# BLE_Controller.net
KiCad netlist of a schematic drawn in Altium Designer
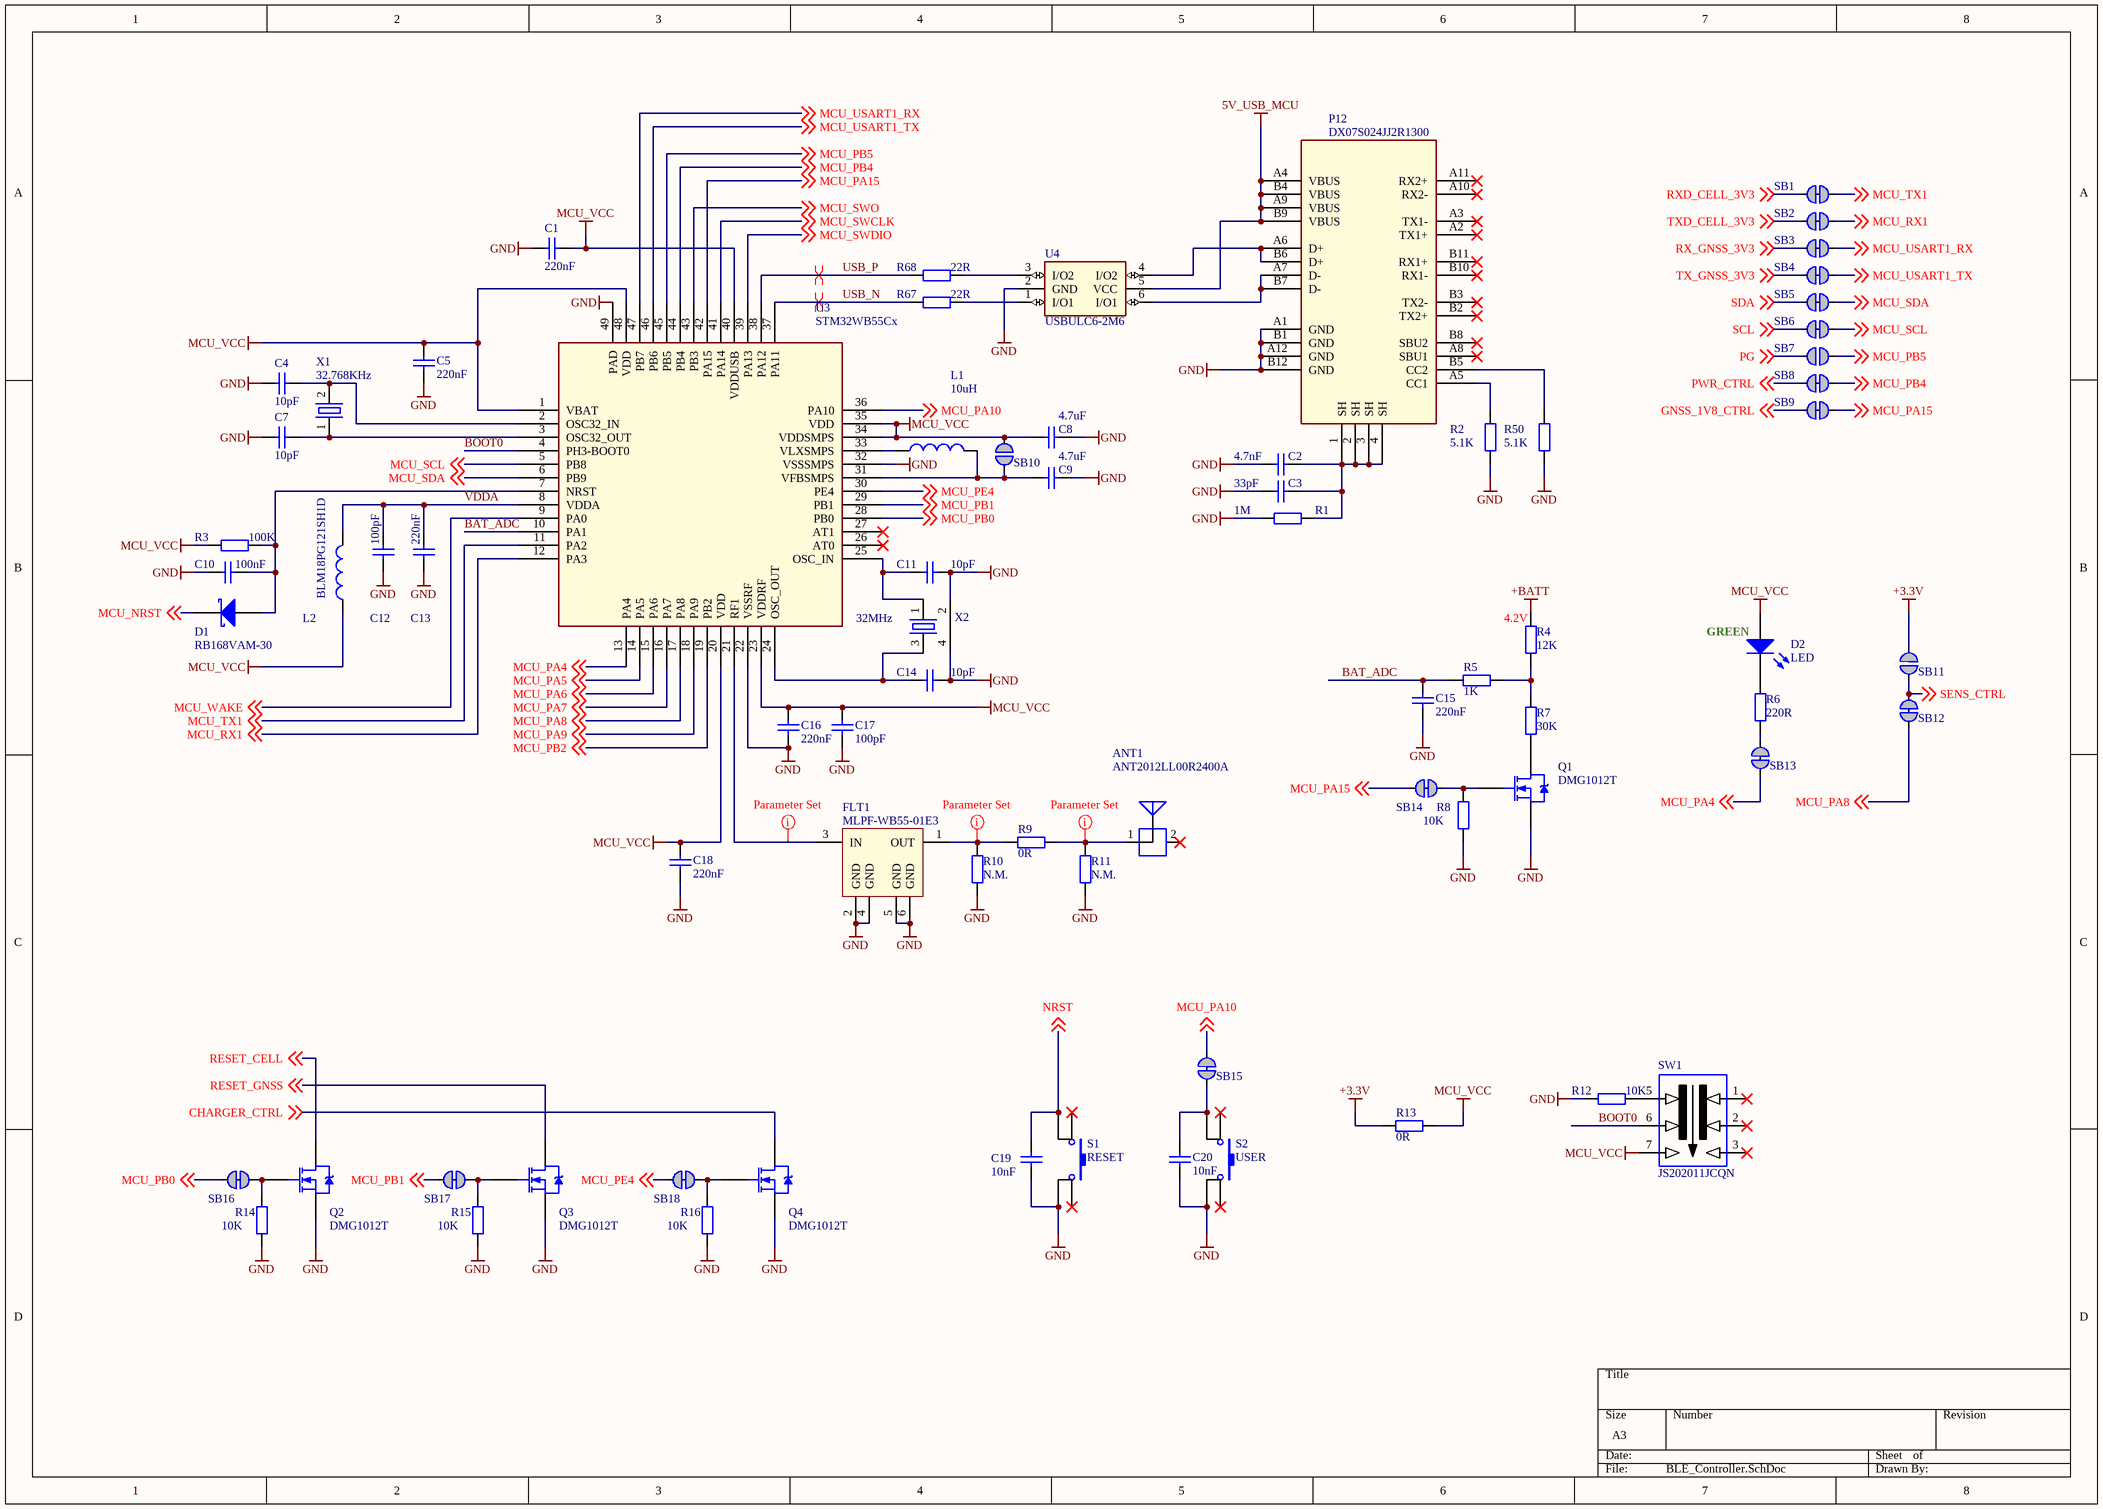
[diagram p0: BLE_Controller.SchDoc]

(export (version "E")
  (design (tool "Eeschema 10.0.6"))
  (components
    (comp (ref "ANT1")
      (value "ANT2012LL00R2400A")
      (footprint "YEGEO_BT_Antena_0805")
      (description "Generic Antenna")
      (fields (field (name "MANUFACTURER") "YAGEO"))
      (libsource (lib "RUT_GE310_GNSS") (part "Antenna"))
    )
    (comp (ref "C1")
      (value "220nF")
      (footprint "C0402")
      (description "Capacitor (Semiconductor SIM Model)")
      (fields
        (field (name "MANUFACTURER") "YAGEO")
        (field (name "MANUFACTURER PART NO.") "CC0402JRNPO9BN100")
      )
      (libsource (lib "Miscellaneous Devices") (part "Cap Semi"))
    )
    (comp (ref "C2")
      (value "4.7nF")
      (footprint "C0402")
      (description "Capacitor (Semiconductor SIM Model)")
      (fields
        (field (name "MANUFACTURER") "YAGEO")
        (field (name "MANUFACTURER PART NO.") "CC0402JRNPO9BN100")
      )
      (libsource (lib "Miscellaneous Devices") (part "Cap Semi"))
    )
    (comp (ref "C3")
      (value "33pF")
      (footprint "C0402")
      (description "Capacitor (Semiconductor SIM Model)")
      (fields
        (field (name "MANUFACTURER") "YAGEO")
        (field (name "MANUFACTURER PART NO.") "CC0402JRNPO9BN100")
      )
      (libsource (lib "Miscellaneous Devices") (part "Cap Semi"))
    )
    (comp (ref "C4")
      (value "10pF")
      (footprint "C0402")
      (description "Capacitor (Semiconductor SIM Model)")
      (fields
        (field (name "MANUFACTURER") "YAGEO")
        (field (name "MANUFACTURER PART NO.") "CC0402JRNPO9BN100")
      )
      (libsource (lib "Miscellaneous Devices") (part "Cap Semi"))
    )
    (comp (ref "C5")
      (value "220nF")
      (footprint "C0402")
      (description "Capacitor (Semiconductor SIM Model)")
      (fields
        (field (name "MANUFACTURER") "YAGEO")
        (field (name "MANUFACTURER PART NO.") "CC0402JRNPO9BN100")
      )
      (libsource (lib "Miscellaneous Devices") (part "Cap Semi"))
    )
    (comp (ref "C7")
      (value "10pF")
      (footprint "C0402")
      (description "Capacitor (Semiconductor SIM Model)")
      (fields
        (field (name "MANUFACTURER") "YAGEO")
        (field (name "MANUFACTURER PART NO.") "CC0402JRNPO9BN100")
      )
      (libsource (lib "Miscellaneous Devices") (part "Cap Semi"))
    )
    (comp (ref "C8")
      (value "4.7uF")
      (footprint "C0402")
      (description "Capacitor (Semiconductor SIM Model)")
      (fields
        (field (name "MANUFACTURER") "YAGEO")
        (field (name "MANUFACTURER PART NO.") "CC0402JRNPO9BN100")
      )
      (libsource (lib "Miscellaneous Devices") (part "Cap Semi"))
    )
    (comp (ref "C9")
      (value "4.7uF")
      (footprint "C0402")
      (description "Capacitor (Semiconductor SIM Model)")
      (fields
        (field (name "MANUFACTURER") "YAGEO")
        (field (name "MANUFACTURER PART NO.") "CC0402JRNPO9BN100")
      )
      (libsource (lib "Miscellaneous Devices") (part "Cap Semi"))
    )
    (comp (ref "C10")
      (value "100nF")
      (footprint "C0402")
      (description "Capacitor (Semiconductor SIM Model)")
      (fields
        (field (name "MANUFACTURER") "YAGEO")
        (field (name "MANUFACTURER PART NO.") "CC0402JRNPO9BN100")
      )
      (libsource (lib "Miscellaneous Devices") (part "Cap Semi"))
    )
    (comp (ref "C11")
      (value "10pF")
      (footprint "C0402")
      (description "Capacitor (Semiconductor SIM Model)")
      (fields
        (field (name "MANUFACTURER") "YAGEO")
        (field (name "MANUFACTURER PART NO.") "CC0402JRNPO9BN100")
      )
      (libsource (lib "Miscellaneous Devices") (part "Cap Semi"))
    )
    (comp (ref "C12")
      (value "100pF")
      (footprint "C0402")
      (description "Capacitor (Semiconductor SIM Model)")
      (fields
        (field (name "MANUFACTURER") "YAGEO")
        (field (name "MANUFACTURER PART NO.") "CC0402JRNPO9BN100")
      )
      (libsource (lib "Miscellaneous Devices") (part "Cap Semi"))
    )
    (comp (ref "C13")
      (value "220nF")
      (footprint "C0402")
      (description "Capacitor (Semiconductor SIM Model)")
      (fields
        (field (name "MANUFACTURER") "YAGEO")
        (field (name "MANUFACTURER PART NO.") "CC0402JRNPO9BN100")
      )
      (libsource (lib "Miscellaneous Devices") (part "Cap Semi"))
    )
    (comp (ref "C14")
      (value "10pF")
      (footprint "C0402")
      (description "Capacitor (Semiconductor SIM Model)")
      (fields
        (field (name "MANUFACTURER") "YAGEO")
        (field (name "MANUFACTURER PART NO.") "CC0402JRNPO9BN100")
      )
      (libsource (lib "Miscellaneous Devices") (part "Cap Semi"))
    )
    (comp (ref "C15")
      (value "220nF")
      (footprint "C0402")
      (description "Capacitor (Semiconductor SIM Model)")
      (fields
        (field (name "MANUFACTURER") "YAGEO")
        (field (name "MANUFACTURER PART NO.") "CC0402KRX5R5BB224")
      )
      (libsource (lib "Miscellaneous Devices") (part "Cap Semi"))
    )
    (comp (ref "C16")
      (value "220nF")
      (footprint "C0402")
      (description "Capacitor (Semiconductor SIM Model)")
      (fields
        (field (name "MANUFACTURER") "YAGEO")
        (field (name "MANUFACTURER PART NO.") "CC0402JRNPO9BN100")
      )
      (libsource (lib "Miscellaneous Devices") (part "Cap Semi"))
    )
    (comp (ref "C17")
      (value "100pF")
      (footprint "C0402")
      (description "Capacitor (Semiconductor SIM Model)")
      (fields
        (field (name "MANUFACTURER") "YAGEO")
        (field (name "MANUFACTURER PART NO.") "CC0402JRNPO9BN100")
      )
      (libsource (lib "Miscellaneous Devices") (part "Cap Semi"))
    )
    (comp (ref "C18")
      (value "220nF")
      (footprint "C0402")
      (description "Capacitor (Semiconductor SIM Model)")
      (fields
        (field (name "MANUFACTURER") "YAGEO")
        (field (name "MANUFACTURER PART NO.") "CC0402JRNPO9BN100")
      )
      (libsource (lib "Miscellaneous Devices") (part "Cap Semi"))
    )
    (comp (ref "C19")
      (value "10nF")
      (footprint "C0402")
      (description "Capacitor (Semiconductor SIM Model)")
      (fields
        (field (name "MANUFACTURER") "Samsung Electronics")
        (field (name "MANUFACTURER PART NO.") "CL05B103KB5NNNC")
      )
      (libsource (lib "Miscellaneous Devices") (part "Cap Semi"))
    )
    (comp (ref "C20")
      (value "10nF")
      (footprint "C0402")
      (description "Capacitor (Semiconductor SIM Model)")
      (fields
        (field (name "MANUFACTURER") "Samsung Electronics")
        (field (name "MANUFACTURER PART NO.") "CL05B103KB5NNNC")
      )
      (libsource (lib "Miscellaneous Devices") (part "Cap Semi"))
    )
    (comp (ref "D1")
      (value "RB168VAM-30")
      (footprint "SOD323")
      (description "Schottky Diode")
      (fields (field (name "MANUFACTURER") "ROHM"))
      (libsource (lib "Miscellaneous Devices") (part "D Schottky"))
    )
    (comp (ref "D2")
      (value "LED")
      (footprint "PICOLED")
      (description "Typical SMD LED")
      (fields (field (name "MANUFACTURER") "ROHM") (field (name "MANUFACTURER PART NO.") "SML-P13PTT86R"))
      (libsource (lib "Miscellaneous Devices") (part "LED2"))
    )
    (comp (ref "FLT1")
      (value "MLPF-WB55-01E3")
      (footprint "Bumpless CSP")
      (description "2.4 GHz low pass filter matched to STM32WB55Cx/Rx")
      (fields (field (name "MANUFACTURER") "STMicroelectronics"))
      (libsource (lib "MLPF-WB55-01E3") (part "MLPF-WB55-01E3"))
    )
    (comp (ref "L1")
      (value "10uH")
      (footprint "L0805")
      (description "Inductor")
      (fields (field (name "MANUFACTURER") "muRata") (field (name "MANUFACTURER PART NO.") "LQM21FN100M70L"))
      (libsource (lib "Miscellaneous Devices") (part "Inductor"))
    )
    (comp (ref "L2")
      (value "BLM18PG121SH1D")
      (footprint "L0603")
      (description "Inductor")
      (fields (field (name "MANUFACTURER") "muRata"))
      (libsource (lib "Miscellaneous Devices") (part "Inductor"))
    )
    (comp (ref "P12")
      (value "DX07S024JJ2R1300")
      (footprint "DX07_USB_C")
      (description "24P USB C DUAL SMT ON BOARD")
      (fields (field (name "MANUFACTURER") "JAE"))
      (libsource (lib "DX07S024JJ2R1300") (part "DX07S024JJ2R1300"))
    )
    (comp (ref "Q1")
      (value "DMG1012T")
      (footprint "SOT-523_custom")
      (description "N-Channel Power MOSFET")
      (fields (field (name "MANUFACTURER") "Diodes Inc.") (field (name "MANUFACTURER PART NO.") "DMG1012T-7"))
      (libsource (lib "Miscellaneous Devices") (part "NMOS-2"))
    )
    (comp (ref "Q2")
      (value "DMG1012T")
      (footprint "SOT-523_custom")
      (description "N-Channel Power MOSFET")
      (fields (field (name "MANUFACTURER") "Diodes Inc.") (field (name "MANUFACTURER PART NO.") "DMG1012T-7"))
      (libsource (lib "Miscellaneous Devices") (part "NMOS-2"))
    )
    (comp (ref "Q3")
      (value "DMG1012T")
      (footprint "SOT-523_custom")
      (description "N-Channel Power MOSFET")
      (fields (field (name "MANUFACTURER") "Diodes Inc.") (field (name "MANUFACTURER PART NO.") "DMG1012T-7"))
      (libsource (lib "Miscellaneous Devices") (part "NMOS-2"))
    )
    (comp (ref "Q4")
      (value "DMG1012T")
      (footprint "SOT-523_custom")
      (description "N-Channel Power MOSFET")
      (fields (field (name "MANUFACTURER") "Diodes Inc.") (field (name "MANUFACTURER PART NO.") "DMG1012T-7"))
      (libsource (lib "Miscellaneous Devices") (part "NMOS-2"))
    )
    (comp (ref "R1")
      (value "1M")
      (footprint "R0402")
      (fields
        (field (name "MANUFACTURER") "YAGEO")
        (field (name "MANUFACTURER PART NO.") "RC0402FR-070RL")
        (field (name "Comment") "Res2")
      )
      (libsource (lib "") (part "Res2_2"))
    )
    (comp (ref "R2")
      (value "5.1K")
      (footprint "R0402")
      (fields
        (field (name "MANUFACTURER") "ASJ")
        (field (name "MANUFACTURER PART NO.") "CR10-103-JK")
        (field (name "Comment") "Res2")
      )
      (libsource (lib "") (part "Res2_1"))
    )
    (comp (ref "R3")
      (value "100K")
      (footprint "R0402")
      (fields
        (field (name "MANUFACTURER") "ASJ")
        (field (name "MANUFACTURER PART NO.") "CR10-103-JK")
        (field (name "Comment") "Res2")
      )
      (libsource (lib "") (part "Res2_2"))
    )
    (comp (ref "R4")
      (value "12K")
      (footprint "R0402")
      (fields
        (field (name "MANUFACTURER") "ASJ")
        (field (name "MANUFACTURER PART NO.") "CR10-105-JK")
        (field (name "Comment") "Res2")
      )
      (libsource (lib "Miscellaneous Devices") (part "Res2"))
    )
    (comp (ref "R5")
      (value "1K")
      (footprint "R0402")
      (fields
        (field (name "MANUFACTURER") "ASJ")
        (field (name "MANUFACTURER PART NO.") "CR10-102-JK")
        (field (name "Comment") "Res2")
      )
      (libsource (lib "") (part "Res2_2"))
    )
    (comp (ref "R6")
      (value "220R")
      (footprint "R0402")
      (fields
        (field (name "MANUFACTURER") "ASJ")
        (field (name "MANUFACTURER PART NO.") "CR10-221-JK")
        (field (name "Comment") "Res2")
      )
      (libsource (lib "Miscellaneous Devices") (part "Res2"))
    )
    (comp (ref "R7")
      (value "30K")
      (footprint "R0402")
      (fields
        (field (name "MANUFACTURER") "YAGEO")
        (field (name "MANUFACTURER PART NO.") "RC0402JR-07390KL")
        (field (name "Comment") "Res2")
      )
      (libsource (lib "Miscellaneous Devices") (part "Res2"))
    )
    (comp (ref "R8")
      (value "10K")
      (footprint "R0402")
      (fields
        (field (name "MANUFACTURER") "ASJ")
        (field (name "MANUFACTURER PART NO.") "CR10-103-JK")
        (field (name "Comment") "Res2")
      )
      (libsource (lib "") (part "Res2_1"))
    )
    (comp (ref "R9")
      (value "0R")
      (footprint "R0402")
      (fields
        (field (name "MANUFACTURER") "YAGEO")
        (field (name "MANUFACTURER PART NO.") "RC0402FR-070RL")
        (field (name "Comment") "Res2")
      )
      (libsource (lib "") (part "Res2_3"))
    )
    (comp (ref "R10")
      (value "N.M.")
      (footprint "R0402")
      (fields
        (field (name "MANUFACTURER") "YAGEO")
        (field (name "MANUFACTURER PART NO.") "RC0402FR-070RL")
        (field (name "Comment") "Res2")
      )
      (libsource (lib "Miscellaneous Devices") (part "Res2"))
    )
    (comp (ref "R11")
      (value "N.M.")
      (footprint "R0402")
      (fields
        (field (name "MANUFACTURER") "YAGEO")
        (field (name "MANUFACTURER PART NO.") "RC0402FR-070RL")
        (field (name "Comment") "Res2")
      )
      (libsource (lib "Miscellaneous Devices") (part "Res2"))
    )
    (comp (ref "R12")
      (value "10K")
      (footprint "R0402")
      (fields
        (field (name "MANUFACTURER") "ASJ")
        (field (name "MANUFACTURER PART NO.") "CR10-103-JK")
        (field (name "Comment") "Res2")
      )
      (libsource (lib "") (part "Res2_2"))
    )
    (comp (ref "R13")
      (value "0R")
      (footprint "R0402")
      (fields
        (field (name "MANUFACTURER") "YAGEO")
        (field (name "MANUFACTURER PART NO.") "RC0402FR-070RL")
        (field (name "Comment") "Res2")
      )
      (libsource (lib "") (part "Res2_3"))
    )
    (comp (ref "R14")
      (value "10K")
      (footprint "R0402")
      (fields
        (field (name "MANUFACTURER") "ASJ")
        (field (name "MANUFACTURER PART NO.") "CR10-103-JK")
        (field (name "Comment") "Res2")
      )
      (libsource (lib "") (part "Res2_1"))
    )
    (comp (ref "R15")
      (value "10K")
      (footprint "R0402")
      (fields
        (field (name "MANUFACTURER") "ASJ")
        (field (name "MANUFACTURER PART NO.") "CR10-103-JK")
        (field (name "Comment") "Res2")
      )
      (libsource (lib "") (part "Res2_1"))
    )
    (comp (ref "R16")
      (value "10K")
      (footprint "R0402")
      (fields
        (field (name "MANUFACTURER") "ASJ")
        (field (name "MANUFACTURER PART NO.") "CR10-103-JK")
        (field (name "Comment") "Res2")
      )
      (libsource (lib "") (part "Res2_1"))
    )
    (comp (ref "R50")
      (value "5.1K")
      (footprint "R0402")
      (fields
        (field (name "MANUFACTURER") "ASJ")
        (field (name "MANUFACTURER PART NO.") "CR10-103-JK")
        (field (name "Comment") "Res2")
      )
      (libsource (lib "") (part "Res2_1"))
    )
    (comp (ref "R67")
      (value "22R")
      (footprint "R0402")
      (fields
        (field (name "MANUFACTURER") "ASJ")
        (field (name "MANUFACTURER PART NO.") "CR10-103-JK")
        (field (name "Comment") "Res2")
      )
      (libsource (lib "") (part "Res2_3"))
    )
    (comp (ref "R68")
      (value "22R")
      (footprint "R0402")
      (fields
        (field (name "MANUFACTURER") "ASJ")
        (field (name "MANUFACTURER PART NO.") "CR10-103-JK")
        (field (name "Comment") "Res2")
      )
      (libsource (lib "") (part "Res2_3"))
    )
    (comp (ref "S1")
      (value "RESET")
      (footprint "PTS645S_button")
      (description "Switch")
      (fields
        (field (name "MANUFACTURER") "C&K")
        (field (name "MANUFACTURER PART NO.") "PTS645SM43SMTR92 LFS")
      )
      (libsource (lib "RUT_L865_Project_1") (part "SW-PB"))
    )
    (comp (ref "S2")
      (value "USER")
      (footprint "PTS645S_button")
      (description "Switch")
      (fields
        (field (name "MANUFACTURER") "C&K")
        (field (name "MANUFACTURER PART NO.") "PTS645SM43SMTR92 LFS")
      )
      (libsource (lib "RUT_L865_Project_1") (part "SW-PB"))
    )
    (comp (ref "SB1")
      (value "Solderbridge")
      (footprint "Solderbridge_Shorted")
      (libsource (lib "altium-import") (part "root_0_SOLDERBRIDGE_SHORTED_"))
    )
    (comp (ref "SB2")
      (value "Solderbridge")
      (footprint "Solderbridge_Shorted")
      (libsource (lib "altium-import") (part "root_0_SOLDERBRIDGE_SHORTED_"))
    )
    (comp (ref "SB3")
      (value "Solderbridge")
      (footprint "Solderbridge_Shorted")
      (libsource (lib "altium-import") (part "root_0_SOLDERBRIDGE_SHORTED_"))
    )
    (comp (ref "SB4")
      (value "Solderbridge")
      (footprint "Solderbridge_Shorted")
      (libsource (lib "altium-import") (part "root_0_SOLDERBRIDGE_SHORTED_"))
    )
    (comp (ref "SB5")
      (value "Solderbridge")
      (footprint "Solderbridge_Shorted")
      (libsource (lib "altium-import") (part "root_0_SOLDERBRIDGE_SHORTED_"))
    )
    (comp (ref "SB6")
      (value "Solderbridge")
      (footprint "Solderbridge_Shorted")
      (libsource (lib "altium-import") (part "root_0_SOLDERBRIDGE_SHORTED_"))
    )
    (comp (ref "SB7")
      (value "Solderbridge")
      (footprint "Solderbridge")
      (libsource (lib "altium-import") (part "root_2_SOLDERBRIDGE_"))
    )
    (comp (ref "SB8")
      (value "Solderbridge")
      (footprint "Solderbridge_Shorted")
      (libsource (lib "altium-import") (part "root_0_SOLDERBRIDGE_SHORTED_"))
    )
    (comp (ref "SB9")
      (value "Solderbridge")
      (footprint "Solderbridge_Shorted")
      (libsource (lib "altium-import") (part "root_0_SOLDERBRIDGE_SHORTED_"))
    )
    (comp (ref "SB10")
      (value "Solderbridge")
      (footprint "Solderbridge")
      (libsource (lib "altium-import") (part "root_3_SOLDERBRIDGE_"))
    )
    (comp (ref "SB11")
      (value "Solderbridge")
      (footprint "Solderbridge")
      (libsource (lib "altium-import") (part "root_1_SOLDERBRIDGE_"))
    )
    (comp (ref "SB12")
      (value "Solderbridge")
      (footprint "Solderbridge_Shorted")
      (libsource (lib "altium-import") (part "root_3_SOLDERBRIDGE_SHORTED_"))
    )
    (comp (ref "SB13")
      (value "Solderbridge")
      (footprint "Solderbridge_Shorted")
      (libsource (lib "altium-import") (part "root_1_SOLDERBRIDGE_SHORTED_"))
    )
    (comp (ref "SB14")
      (value "Solderbridge")
      (footprint "Solderbridge_Shorted")
      (libsource (lib "altium-import") (part "root_0_SOLDERBRIDGE_SHORTED_"))
    )
    (comp (ref "SB15")
      (value "Solderbridge")
      (footprint "Solderbridge_Shorted")
      (libsource (lib "altium-import") (part "root_1_SOLDERBRIDGE_SHORTED_"))
    )
    (comp (ref "SB16")
      (value "Solderbridge")
      (footprint "Solderbridge_Shorted")
      (libsource (lib "altium-import") (part "root_0_SOLDERBRIDGE_SHORTED_"))
    )
    (comp (ref "SB17")
      (value "Solderbridge")
      (footprint "Solderbridge_Shorted")
      (libsource (lib "altium-import") (part "root_0_SOLDERBRIDGE_SHORTED_"))
    )
    (comp (ref "SB18")
      (value "Solderbridge")
      (footprint "Solderbridge_Shorted")
      (libsource (lib "altium-import") (part "root_0_SOLDERBRIDGE_SHORTED_"))
    )
    (comp (ref "SW1")
      (value "JS202011JCQN")
      (footprint "JS202011JCQN")
      (description "Sub-Miniature Slide Switch, VERTICAL MOUNT SMT - J BEND")
      (fields (field (name "MANUFACTURER") "CK Switches"))
      (libsource (lib "JS202011JCQN") (part "JS202011JCQN"))
    )
    (comp (ref "U3")
      (value "STM32WB55Cx")
      (footprint "UFQFPN48")
      (fields
        (field (name "MANUFACTURER") "STMicroelectronics")
        (field (name "MANUFACTURER PART NO.") "STM32WB55CGU6")
      )
      (libsource (lib "RUT2CLOUDPrjPcb") (part "STM32WBxx_QFN48"))
    )
    (comp (ref "U4")
      (value "USBULC6-2M6")
      (footprint "Micro_QFN_6L")
      (description "Ultra large bandwidth ESD protection")
      (fields (field (name "MANUFACTURER") "STMicroelectronics"))
      (libsource (lib "USBULC6-2M6") (part "USBULC6-2M6"))
    )
    (comp (ref "X1")
      (value "32.768KHz")
      (footprint "XTAL_3215")
      (fields
        (field (name "MANUFACTURER") "Epson Electronics")
        (field (name "MANUFACTURER PART NO.") "FC-135 32.7680KA-AC3")
      )
      (libsource (lib "RUT_L865_Project_1") (part "XTL-000011-01"))
    )
    (comp (ref "X2")
      (value "32MHz")
      (footprint "XTAL_3.5x2.5")
      (fields
        (field (name "MANUFACTURER") "Kyocera")
        (field (name "MANUFACTURER PART NO.") "CX3225SB32000D0FLJCC")
      )
      (libsource (lib "") (part "XTL-000011-01_1"))
    )
  )
  (nets
    (net (code "1") (name "+3.3V") (class "Default")
      (node (ref "R13") (pin "2") (pinfunction "2_2") (pintype "passive"))
      (node (ref "SB11") (pin "1") (pinfunction "0_1") (pintype "passive"))
    )
    (net (code "2") (name "+BATT") (class "Default")
      (node (ref "R4") (pin "1") (pinfunction "1_1") (pintype "passive"))
    )
    (net (code "3") (name "/BAT_ADC") (class "Default")
      (node (ref "C15") (pin "1") (pinfunction "1_1") (pintype "passive"))
      (node (ref "R5") (pin "1") (pinfunction "1_1") (pintype "passive"))
      (node (ref "U3") (pin "10") (pinfunction "PA1_10") (pintype "passive"))
    )
    (net (code "4") (name "/BOOT0") (class "Default")
      (node (ref "SW1") (pin "6") (pinfunction "6_6") (pintype "passive"))
      (node (ref "U3") (pin "4") (pinfunction "PH3-BOOT0_4") (pintype "passive"))
    )
    (net (code "5") (name "/USB_N") (class "Default")
      (node (ref "R67") (pin "2") (pinfunction "2_2") (pintype "passive"))
      (node (ref "U3") (pin "37") (pinfunction "PA11_37") (pintype "passive"))
    )
    (net (code "6") (name "/USB_P") (class "Default")
      (node (ref "R68") (pin "2") (pinfunction "2_2") (pintype "passive"))
      (node (ref "U3") (pin "38") (pinfunction "PA12_38") (pintype "passive"))
    )
    (net (code "7") (name "/VDDA") (class "Default")
      (node (ref "C12") (pin "2") (pinfunction "2_2") (pintype "passive"))
      (node (ref "C13") (pin "2") (pinfunction "2_2") (pintype "passive"))
      (node (ref "L2") (pin "2") (pinfunction "2_2") (pintype "passive"))
      (node (ref "U3") (pin "8") (pinfunction "VDDA_8") (pintype "passive"))
    )
    (net (code "8") (name "5V_USB_MCU") (class "Default")
      (node (ref "P12") (pin "A4") (pinfunction "VBUS_A4") (pintype "passive"))
      (node (ref "P12") (pin "A9") (pinfunction "VBUS_A9") (pintype "passive"))
      (node (ref "P12") (pin "B4") (pinfunction "VBUS_B4") (pintype "passive"))
      (node (ref "P12") (pin "B9") (pinfunction "VBUS_B9") (pintype "passive"))
      (node (ref "U4") (pin "5") (pinfunction "VCC_5") (pintype "power_in"))
    )
    (net (code "9") (name "CHARGER_CTRL") (class "Default")
      (node (ref "Q4") (pin "2") (pinfunction "D_2") (pintype "passive"))
    )
    (net (code "10") (name "GND") (class "Default")
      (node (ref "C1") (pin "2") (pinfunction "2_2") (pintype "passive"))
      (node (ref "C10") (pin "1") (pinfunction "1_1") (pintype "passive"))
      (node (ref "C11") (pin "2") (pinfunction "2_2") (pintype "passive"))
      (node (ref "C12") (pin "1") (pinfunction "1_1") (pintype "passive"))
      (node (ref "C13") (pin "1") (pinfunction "1_1") (pintype "passive"))
      (node (ref "C14") (pin "1") (pinfunction "1_1") (pintype "passive"))
      (node (ref "C15") (pin "2") (pinfunction "2_2") (pintype "passive"))
      (node (ref "C16") (pin "1") (pinfunction "1_1") (pintype "passive"))
      (node (ref "C17") (pin "1") (pinfunction "1_1") (pintype "passive"))
      (node (ref "C18") (pin "1") (pinfunction "1_1") (pintype "passive"))
      (node (ref "C19") (pin "1") (pinfunction "1_1") (pintype "passive"))
      (node (ref "C2") (pin "1") (pinfunction "1_1") (pintype "passive"))
      (node (ref "C20") (pin "2") (pinfunction "2_2") (pintype "passive"))
      (node (ref "C3") (pin "1") (pinfunction "1_1") (pintype "passive"))
      (node (ref "C4") (pin "1") (pinfunction "1_1") (pintype "passive"))
      (node (ref "C5") (pin "1") (pinfunction "1_1") (pintype "passive"))
      (node (ref "C7") (pin "2") (pinfunction "2_2") (pintype "passive"))
      (node (ref "C8") (pin "2") (pinfunction "2_2") (pintype "passive"))
      (node (ref "C9") (pin "2") (pinfunction "2_2") (pintype "passive"))
      (node (ref "FLT1") (pin "2") (pinfunction "GND_2") (pintype "passive"))
      (node (ref "FLT1") (pin "4") (pinfunction "GND_4") (pintype "passive"))
      (node (ref "FLT1") (pin "5") (pinfunction "GND_5") (pintype "passive"))
      (node (ref "FLT1") (pin "6") (pinfunction "GND_6") (pintype "passive"))
      (node (ref "P12") (pin "A1") (pinfunction "GND_A1") (pintype "passive"))
      (node (ref "P12") (pin "A12") (pinfunction "GND_A12") (pintype "passive"))
      (node (ref "P12") (pin "B1") (pinfunction "GND_B1") (pintype "passive"))
      (node (ref "P12") (pin "B12") (pinfunction "GND_B12") (pintype "passive"))
      (node (ref "Q1") (pin "3") (pinfunction "S_3") (pintype "passive"))
      (node (ref "Q2") (pin "3") (pinfunction "S_3") (pintype "passive"))
      (node (ref "Q3") (pin "3") (pinfunction "S_3") (pintype "passive"))
      (node (ref "Q4") (pin "3") (pinfunction "S_3") (pintype "passive"))
      (node (ref "R1") (pin "1") (pinfunction "1_1") (pintype "passive"))
      (node (ref "R10") (pin "2") (pinfunction "2_2") (pintype "passive"))
      (node (ref "R11") (pin "2") (pinfunction "2_2") (pintype "passive"))
      (node (ref "R12") (pin "1") (pinfunction "1_1") (pintype "passive"))
      (node (ref "R14") (pin "1") (pinfunction "1_1") (pintype "passive"))
      (node (ref "R15") (pin "1") (pinfunction "1_1") (pintype "passive"))
      (node (ref "R16") (pin "1") (pinfunction "1_1") (pintype "passive"))
      (node (ref "R2") (pin "1") (pinfunction "1_1") (pintype "passive"))
      (node (ref "R50") (pin "1") (pinfunction "1_1") (pintype "passive"))
      (node (ref "R8") (pin "1") (pinfunction "1_1") (pintype "passive"))
      (node (ref "S1") (pin "4") (pinfunction "4_4") (pintype "passive"))
      (node (ref "S2") (pin "4") (pinfunction "4_4") (pintype "passive"))
      (node (ref "U3") (pin "22") (pinfunction "VSSRF_22") (pintype "passive"))
      (node (ref "U3") (pin "32") (pinfunction "VSSSMPS_32") (pintype "passive"))
      (node (ref "U3") (pin "49") (pinfunction "PAD_49") (pintype "power_in"))
      (node (ref "U4") (pin "2") (pinfunction "GND_2") (pintype "power_in"))
      (node (ref "X2") (pin "2") (pinfunction "2_2") (pintype "passive"))
      (node (ref "X2") (pin "4") (pinfunction "4_4") (pintype "passive"))
    )
    (net (code "11") (name "GNSS_1V8_CTRL") (class "Default")
      (node (ref "SB9") (pin "2") (pinfunction "1_2") (pintype "passive"))
    )
    (net (code "12") (name "MCU_NRST") (class "Default")
      (node (ref "D1") (pin "2") (pinfunction "K_2") (pintype "passive"))
    )
    (net (code "13") (name "MCU_PA4") (class "Default")
      (node (ref "SB13") (pin "2") (pinfunction "1_2") (pintype "passive"))
      (node (ref "U3") (pin "13") (pinfunction "PA4_13") (pintype "passive"))
    )
    (net (code "14") (name "MCU_PA5") (class "Default")
      (node (ref "U3") (pin "14") (pinfunction "PA5_14") (pintype "passive"))
    )
    (net (code "15") (name "MCU_PA6") (class "Default")
      (node (ref "U3") (pin "15") (pinfunction "PA6_15") (pintype "passive"))
    )
    (net (code "16") (name "MCU_PA7") (class "Default")
      (node (ref "U3") (pin "16") (pinfunction "PA7_16") (pintype "passive"))
    )
    (net (code "17") (name "MCU_PA8") (class "Default")
      (node (ref "SB12") (pin "1") (pinfunction "0_1") (pintype "passive"))
      (node (ref "U3") (pin "17") (pinfunction "PA8_17") (pintype "passive"))
    )
    (net (code "18") (name "MCU_PA9") (class "Default")
      (node (ref "U3") (pin "18") (pinfunction "PA9_18") (pintype "passive"))
    )
    (net (code "19") (name "MCU_PA10") (class "Default")
      (node (ref "SB15") (pin "1") (pinfunction "0_1") (pintype "passive"))
      (node (ref "U3") (pin "36") (pinfunction "PA10_36") (pintype "passive"))
    )
    (net (code "20") (name "MCU_PA15") (class "Default")
      (node (ref "SB14") (pin "2") (pinfunction "1_2") (pintype "passive"))
      (node (ref "SB9") (pin "1") (pinfunction "0_1") (pintype "passive"))
      (node (ref "U3") (pin "42") (pinfunction "PA15_42") (pintype "passive"))
    )
    (net (code "21") (name "MCU_PB0") (class "Default")
      (node (ref "SB16") (pin "2") (pinfunction "1_2") (pintype "passive"))
      (node (ref "U3") (pin "28") (pinfunction "PB0_28") (pintype "passive"))
    )
    (net (code "22") (name "MCU_PB1") (class "Default")
      (node (ref "SB17") (pin "2") (pinfunction "1_2") (pintype "passive"))
      (node (ref "U3") (pin "29") (pinfunction "PB1_29") (pintype "passive"))
    )
    (net (code "23") (name "MCU_PB2") (class "Default")
      (node (ref "U3") (pin "19") (pinfunction "PB2_19") (pintype "passive"))
    )
    (net (code "24") (name "MCU_PB4") (class "Default")
      (node (ref "SB8") (pin "1") (pinfunction "0_1") (pintype "passive"))
      (node (ref "U3") (pin "44") (pinfunction "PB4_44") (pintype "passive"))
    )
    (net (code "25") (name "MCU_PB5") (class "Default")
      (node (ref "SB7") (pin "2") (pinfunction "1_2") (pintype "passive"))
      (node (ref "U3") (pin "45") (pinfunction "PB5_45") (pintype "passive"))
    )
    (net (code "26") (name "MCU_PE4") (class "Default")
      (node (ref "SB18") (pin "2") (pinfunction "1_2") (pintype "passive"))
      (node (ref "U3") (pin "30") (pinfunction "PE4_30") (pintype "passive"))
    )
    (net (code "27") (name "MCU_RX1") (class "Default")
      (node (ref "SB2") (pin "1") (pinfunction "0_1") (pintype "passive"))
      (node (ref "U3") (pin "12") (pinfunction "PA3_12") (pintype "passive"))
    )
    (net (code "28") (name "MCU_SCL") (class "Default")
      (node (ref "SB6") (pin "1") (pinfunction "0_1") (pintype "passive"))
      (node (ref "U3") (pin "5") (pinfunction "PB8_5") (pintype "passive"))
    )
    (net (code "29") (name "MCU_SDA") (class "Default")
      (node (ref "SB5") (pin "1") (pinfunction "0_1") (pintype "passive"))
      (node (ref "U3") (pin "6") (pinfunction "PB9_6") (pintype "passive"))
    )
    (net (code "30") (name "MCU_SWCLK") (class "Default")
      (node (ref "U3") (pin "41") (pinfunction "PA14_41") (pintype "passive"))
    )
    (net (code "31") (name "MCU_SWDIO") (class "Default")
      (node (ref "U3") (pin "39") (pinfunction "PA13_39") (pintype "passive"))
    )
    (net (code "32") (name "MCU_SWO") (class "Default")
      (node (ref "U3") (pin "43") (pinfunction "PB3_43") (pintype "passive"))
    )
    (net (code "33") (name "MCU_TX1") (class "Default")
      (node (ref "SB1") (pin "1") (pinfunction "0_1") (pintype "passive"))
      (node (ref "U3") (pin "11") (pinfunction "PA2_11") (pintype "passive"))
    )
    (net (code "34") (name "MCU_USART1_RX") (class "Default")
      (node (ref "SB3") (pin "1") (pinfunction "0_1") (pintype "passive"))
      (node (ref "U3") (pin "47") (pinfunction "PB7_47") (pintype "passive"))
    )
    (net (code "35") (name "MCU_USART1_TX") (class "Default")
      (node (ref "SB4") (pin "1") (pinfunction "0_1") (pintype "passive"))
      (node (ref "U3") (pin "46") (pinfunction "PB6_46") (pintype "passive"))
    )
    (net (code "36") (name "MCU_VCC") (class "Default")
      (node (ref "C1") (pin "1") (pinfunction "1_1") (pintype "passive"))
      (node (ref "C16") (pin "2") (pinfunction "2_2") (pintype "passive"))
      (node (ref "C17") (pin "2") (pinfunction "2_2") (pintype "passive"))
      (node (ref "C18") (pin "2") (pinfunction "2_2") (pintype "passive"))
      (node (ref "C5") (pin "2") (pinfunction "2_2") (pintype "passive"))
      (node (ref "C8") (pin "1") (pinfunction "1_1") (pintype "passive"))
      (node (ref "D2") (pin "1") (pinfunction "A_1") (pintype "passive"))
      (node (ref "L2") (pin "1") (pinfunction "1_1") (pintype "passive"))
      (node (ref "R13") (pin "1") (pinfunction "1_1") (pintype "passive"))
      (node (ref "R3") (pin "1") (pinfunction "1_1") (pintype "passive"))
      (node (ref "SB10") (pin "2") (pinfunction "1_2") (pintype "passive"))
      (node (ref "SW1") (pin "7") (pinfunction "7_7") (pintype "passive"))
      (node (ref "U3") (pin "1") (pinfunction "VBAT_1") (pintype "passive"))
      (node (ref "U3") (pin "20") (pinfunction "VDD_20") (pintype "passive"))
      (node (ref "U3") (pin "23") (pinfunction "VDDRF_23") (pintype "passive"))
      (node (ref "U3") (pin "34") (pinfunction "VDDSMPS_34") (pintype "passive"))
      (node (ref "U3") (pin "35") (pinfunction "VDD_35") (pintype "passive"))
      (node (ref "U3") (pin "40") (pinfunction "VDDUSB_40") (pintype "passive"))
      (node (ref "U3") (pin "48") (pinfunction "VDD_48") (pintype "power_in"))
    )
    (net (code "37") (name "MCU_WAKE") (class "Default")
      (node (ref "U3") (pin "9") (pinfunction "PA0_9") (pintype "passive"))
    )
    (net (code "38") (name "NRST") (class "Default")
      (node (ref "C19") (pin "2") (pinfunction "2_2") (pintype "passive"))
      (node (ref "S1") (pin "2") (pinfunction "2_2") (pintype "passive"))
    )
    (net (code "39") (name "Net-(ANT1-Pad1)") (class "Default")
      (node (ref "ANT1") (pin "1") (pinfunction "1_1") (pintype "passive"))
      (node (ref "R11") (pin "1") (pinfunction "1_1") (pintype "passive"))
      (node (ref "R9") (pin "1") (pinfunction "1_1") (pintype "passive"))
    )
    (net (code "40") (name "Net-(C2-Pad2)") (class "Default")
      (node (ref "C2") (pin "2") (pinfunction "2_2") (pintype "passive"))
      (node (ref "C3") (pin "2") (pinfunction "2_2") (pintype "passive"))
      (node (ref "P12") (pin "1") (pinfunction "SH_1") (pintype "passive"))
      (node (ref "P12") (pin "2") (pinfunction "SH_2") (pintype "passive"))
      (node (ref "P12") (pin "3") (pinfunction "SH_3") (pintype "passive"))
      (node (ref "P12") (pin "4") (pinfunction "SH_4") (pintype "passive"))
      (node (ref "R1") (pin "2") (pinfunction "2_2") (pintype "passive"))
    )
    (net (code "41") (name "Net-(D1-A)") (class "Default")
      (node (ref "C10") (pin "2") (pinfunction "2_2") (pintype "passive"))
      (node (ref "D1") (pin "1") (pinfunction "A_1") (pintype "passive"))
      (node (ref "R3") (pin "2") (pinfunction "2_2") (pintype "passive"))
      (node (ref "U3") (pin "7") (pinfunction "NRST_7") (pintype "passive"))
    )
    (net (code "42") (name "Net-(D2-K)") (class "Default")
      (node (ref "D2") (pin "2") (pinfunction "K_2") (pintype "passive"))
      (node (ref "R6") (pin "1") (pinfunction "1_1") (pintype "passive"))
    )
    (net (code "43") (name "Net-(FLT1-IN)") (class "Default")
      (node (ref "FLT1") (pin "3") (pinfunction "IN_3") (pintype "passive"))
      (node (ref "U3") (pin "21") (pinfunction "RF1_21") (pintype "passive"))
    )
    (net (code "44") (name "Net-(FLT1-OUT)") (class "Default")
      (node (ref "FLT1") (pin "1") (pinfunction "OUT_1") (pintype "passive"))
      (node (ref "R10") (pin "1") (pinfunction "1_1") (pintype "passive"))
      (node (ref "R9") (pin "2") (pinfunction "2_2") (pintype "passive"))
    )
    (net (code "45") (name "Net-(P12-CC1)") (class "Default")
      (node (ref "P12") (pin "A5") (pinfunction "CC1_A5") (pintype "passive"))
      (node (ref "R2") (pin "2") (pinfunction "2_2") (pintype "passive"))
    )
    (net (code "46") (name "Net-(P12-CC2)") (class "Default")
      (node (ref "P12") (pin "B5") (pinfunction "CC2_B5") (pintype "passive"))
      (node (ref "R50") (pin "2") (pinfunction "2_2") (pintype "passive"))
    )
    (net (code "47") (name "Net-(P12-D+-PadA6)") (class "Default")
      (node (ref "P12") (pin "A6") (pinfunction "D+_A6") (pintype "passive"))
      (node (ref "P12") (pin "B6") (pinfunction "D+_B6") (pintype "passive"))
      (node (ref "U4") (pin "4") (pinfunction "I/O2_4") (pintype "bidirectional"))
    )
    (net (code "48") (name "Net-(P12-D--PadA7)") (class "Default")
      (node (ref "P12") (pin "A7") (pinfunction "D-_A7") (pintype "passive"))
      (node (ref "P12") (pin "B7") (pinfunction "D-_B7") (pintype "passive"))
      (node (ref "U4") (pin "6") (pinfunction "I/O1_6") (pintype "bidirectional"))
    )
    (net (code "49") (name "Net-(Q1-D)") (class "Default")
      (node (ref "Q1") (pin "2") (pinfunction "D_2") (pintype "passive"))
      (node (ref "R7") (pin "2") (pinfunction "2_2") (pintype "passive"))
    )
    (net (code "50") (name "Net-(Q1-G)") (class "Default")
      (node (ref "Q1") (pin "1") (pinfunction "G_1") (pintype "passive"))
      (node (ref "R8") (pin "2") (pinfunction "2_2") (pintype "passive"))
      (node (ref "SB14") (pin "1") (pinfunction "0_1") (pintype "passive"))
    )
    (net (code "51") (name "Net-(Q2-G)") (class "Default")
      (node (ref "Q2") (pin "1") (pinfunction "G_1") (pintype "passive"))
      (node (ref "R14") (pin "2") (pinfunction "2_2") (pintype "passive"))
      (node (ref "SB16") (pin "1") (pinfunction "0_1") (pintype "passive"))
    )
    (net (code "52") (name "Net-(Q3-G)") (class "Default")
      (node (ref "Q3") (pin "1") (pinfunction "G_1") (pintype "passive"))
      (node (ref "R15") (pin "2") (pinfunction "2_2") (pintype "passive"))
      (node (ref "SB17") (pin "1") (pinfunction "0_1") (pintype "passive"))
    )
    (net (code "53") (name "Net-(Q4-G)") (class "Default")
      (node (ref "Q4") (pin "1") (pinfunction "G_1") (pintype "passive"))
      (node (ref "R16") (pin "2") (pinfunction "2_2") (pintype "passive"))
      (node (ref "SB18") (pin "1") (pinfunction "0_1") (pintype "passive"))
    )
    (net (code "54") (name "Net-(R4-Pad2)") (class "Default")
      (node (ref "R4") (pin "2") (pinfunction "2_2") (pintype "passive"))
      (node (ref "R5") (pin "2") (pinfunction "2_2") (pintype "passive"))
      (node (ref "R7") (pin "1") (pinfunction "1_1") (pintype "passive"))
    )
    (net (code "55") (name "Net-(R12-Pad2)") (class "Default")
      (node (ref "R12") (pin "2") (pinfunction "2_2") (pintype "passive"))
      (node (ref "SW1") (pin "5") (pinfunction "5_5") (pintype "passive"))
    )
    (net (code "56") (name "Net-(R67-Pad1)") (class "Default")
      (node (ref "R67") (pin "1") (pinfunction "1_1") (pintype "passive"))
      (node (ref "U4") (pin "1") (pinfunction "I/O1_1") (pintype "bidirectional"))
    )
    (net (code "57") (name "Net-(R68-Pad1)") (class "Default")
      (node (ref "R68") (pin "1") (pinfunction "1_1") (pintype "passive"))
      (node (ref "U4") (pin "3") (pinfunction "I/O2_3") (pintype "bidirectional"))
    )
    (net (code "58") (name "Net-(SB10-0)") (class "Default")
      (node (ref "C9") (pin "1") (pinfunction "1_1") (pintype "passive"))
      (node (ref "L1") (pin "2") (pinfunction "2_2") (pintype "passive"))
      (node (ref "SB10") (pin "1") (pinfunction "0_1") (pintype "passive"))
      (node (ref "U3") (pin "31") (pinfunction "VFBSMPS_31") (pintype "passive"))
    )
    (net (code "59") (name "Net-(SB13-0)") (class "Default")
      (node (ref "R6") (pin "2") (pinfunction "2_2") (pintype "passive"))
      (node (ref "SB13") (pin "1") (pinfunction "0_1") (pintype "passive"))
    )
    (net (code "60") (name "Net-(SB15-1)") (class "Default")
      (node (ref "C20") (pin "1") (pinfunction "1_1") (pintype "passive"))
      (node (ref "S2") (pin "2") (pinfunction "2_2") (pintype "passive"))
      (node (ref "SB15") (pin "2") (pinfunction "1_2") (pintype "passive"))
    )
    (net (code "61") (name "Net-(U3-OSC32_IN)") (class "Default")
      (node (ref "C4") (pin "2") (pinfunction "2_2") (pintype "passive"))
      (node (ref "U3") (pin "2") (pinfunction "OSC32_IN_2") (pintype "passive"))
      (node (ref "X1") (pin "2") (pinfunction "2_2") (pintype "passive"))
    )
    (net (code "62") (name "Net-(U3-OSC32_OUT)") (class "Default")
      (node (ref "C7") (pin "1") (pinfunction "1_1") (pintype "passive"))
      (node (ref "U3") (pin "3") (pinfunction "OSC32_OUT_3") (pintype "passive"))
      (node (ref "X1") (pin "1") (pinfunction "1_1") (pintype "passive"))
    )
    (net (code "63") (name "Net-(U3-OSC_IN)") (class "Default")
      (node (ref "C11") (pin "1") (pinfunction "1_1") (pintype "passive"))
      (node (ref "U3") (pin "25") (pinfunction "OSC_IN_25") (pintype "passive"))
      (node (ref "X2") (pin "1") (pinfunction "1_1") (pintype "passive"))
    )
    (net (code "64") (name "Net-(U3-OSC_OUT)") (class "Default")
      (node (ref "C14") (pin "2") (pinfunction "2_2") (pintype "passive"))
      (node (ref "U3") (pin "24") (pinfunction "OSC_OUT_24") (pintype "passive"))
      (node (ref "X2") (pin "3") (pinfunction "3_3") (pintype "passive"))
    )
    (net (code "65") (name "Net-(U3-VLXSMPS)") (class "Default")
      (node (ref "L1") (pin "1") (pinfunction "1_1") (pintype "passive"))
      (node (ref "U3") (pin "33") (pinfunction "VLXSMPS_33") (pintype "passive"))
    )
    (net (code "66") (name "PG") (class "Default")
      (node (ref "SB7") (pin "1") (pinfunction "0_1") (pintype "passive"))
    )
    (net (code "67") (name "PWR_CTRL") (class "Default")
      (node (ref "SB8") (pin "2") (pinfunction "1_2") (pintype "passive"))
    )
    (net (code "68") (name "RESET_CELL") (class "Default")
      (node (ref "Q2") (pin "2") (pinfunction "D_2") (pintype "passive"))
    )
    (net (code "69") (name "RESET_GNSS") (class "Default")
      (node (ref "Q3") (pin "2") (pinfunction "D_2") (pintype "passive"))
    )
    (net (code "70") (name "RXD_CELL_3V3") (class "Default")
      (node (ref "SB1") (pin "2") (pinfunction "1_2") (pintype "passive"))
    )
    (net (code "71") (name "RX_GNSS_3V3") (class "Default")
      (node (ref "SB3") (pin "2") (pinfunction "1_2") (pintype "passive"))
    )
    (net (code "72") (name "SCL") (class "Default")
      (node (ref "SB6") (pin "2") (pinfunction "1_2") (pintype "passive"))
    )
    (net (code "73") (name "SDA") (class "Default")
      (node (ref "SB5") (pin "2") (pinfunction "1_2") (pintype "passive"))
    )
    (net (code "74") (name "SENS_CTRL") (class "Default")
      (node (ref "SB11") (pin "2") (pinfunction "1_2") (pintype "passive"))
      (node (ref "SB12") (pin "2") (pinfunction "1_2") (pintype "passive"))
    )
    (net (code "75") (name "TXD_CELL_3V3") (class "Default")
      (node (ref "SB2") (pin "2") (pinfunction "1_2") (pintype "passive"))
    )
    (net (code "76") (name "TX_GNSS_3V3") (class "Default")
      (node (ref "SB4") (pin "2") (pinfunction "1_2") (pintype "passive"))
    )
    (net (code "77") (name "unconnected-(ANT1-Pad2)") (class "Default")
      (node (ref "ANT1") (pin "2") (pinfunction "2_2") (pintype "passive+no_connect"))
    )
    (net (code "78") (name "unconnected-(P12-RX1+-PadB11)") (class "Default")
      (node (ref "P12") (pin "B11") (pinfunction "RX1+_B11") (pintype "passive+no_connect"))
    )
    (net (code "79") (name "unconnected-(P12-RX1--PadB10)") (class "Default")
      (node (ref "P12") (pin "B10") (pinfunction "RX1-_B10") (pintype "passive+no_connect"))
    )
    (net (code "80") (name "unconnected-(P12-RX2+-PadA11)") (class "Default")
      (node (ref "P12") (pin "A11") (pinfunction "RX2+_A11") (pintype "passive+no_connect"))
    )
    (net (code "81") (name "unconnected-(P12-RX2--PadA10)") (class "Default")
      (node (ref "P12") (pin "A10") (pinfunction "RX2-_A10") (pintype "passive+no_connect"))
    )
    (net (code "82") (name "unconnected-(P12-SBU1-PadA8)") (class "Default")
      (node (ref "P12") (pin "A8") (pinfunction "SBU1_A8") (pintype "passive+no_connect"))
    )
    (net (code "83") (name "unconnected-(P12-SBU2-PadB8)") (class "Default")
      (node (ref "P12") (pin "B8") (pinfunction "SBU2_B8") (pintype "passive+no_connect"))
    )
    (net (code "84") (name "unconnected-(P12-TX1+-PadA2)") (class "Default")
      (node (ref "P12") (pin "A2") (pinfunction "TX1+_A2") (pintype "passive+no_connect"))
    )
    (net (code "85") (name "unconnected-(P12-TX1--PadA3)") (class "Default")
      (node (ref "P12") (pin "A3") (pinfunction "TX1-_A3") (pintype "passive+no_connect"))
    )
    (net (code "86") (name "unconnected-(P12-TX2+-PadB2)") (class "Default")
      (node (ref "P12") (pin "B2") (pinfunction "TX2+_B2") (pintype "passive+no_connect"))
    )
    (net (code "87") (name "unconnected-(P12-TX2--PadB3)") (class "Default")
      (node (ref "P12") (pin "B3") (pinfunction "TX2-_B3") (pintype "passive+no_connect"))
    )
    (net (code "88") (name "unconnected-(S1-Pad1)") (class "Default")
      (node (ref "S1") (pin "1") (pinfunction "1_1") (pintype "passive+no_connect"))
    )
    (net (code "89") (name "unconnected-(S1-Pad3)") (class "Default")
      (node (ref "S1") (pin "3") (pinfunction "3_3") (pintype "passive+no_connect"))
    )
    (net (code "90") (name "unconnected-(S2-Pad1)") (class "Default")
      (node (ref "S2") (pin "1") (pinfunction "1_1") (pintype "passive+no_connect"))
    )
    (net (code "91") (name "unconnected-(S2-Pad3)") (class "Default")
      (node (ref "S2") (pin "3") (pinfunction "3_3") (pintype "passive+no_connect"))
    )
    (net (code "92") (name "unconnected-(SW1-Pad1)") (class "Default")
      (node (ref "SW1") (pin "1") (pinfunction "1_1") (pintype "passive+no_connect"))
    )
    (net (code "93") (name "unconnected-(SW1-Pad2)") (class "Default")
      (node (ref "SW1") (pin "2") (pinfunction "2_2") (pintype "passive+no_connect"))
    )
    (net (code "94") (name "unconnected-(SW1-Pad3)") (class "Default")
      (node (ref "SW1") (pin "3") (pinfunction "3_3") (pintype "passive+no_connect"))
    )
    (net (code "95") (name "unconnected-(U3-AT0-Pad26)") (class "Default")
      (node (ref "U3") (pin "26") (pinfunction "AT0_26") (pintype "passive+no_connect"))
    )
    (net (code "96") (name "unconnected-(U3-AT1-Pad27)") (class "Default")
      (node (ref "U3") (pin "27") (pinfunction "AT1_27") (pintype "passive+no_connect"))
    )
  )
)
